# Power_supply.net
KiCad netlist of a schematic drawn in Altium Designer
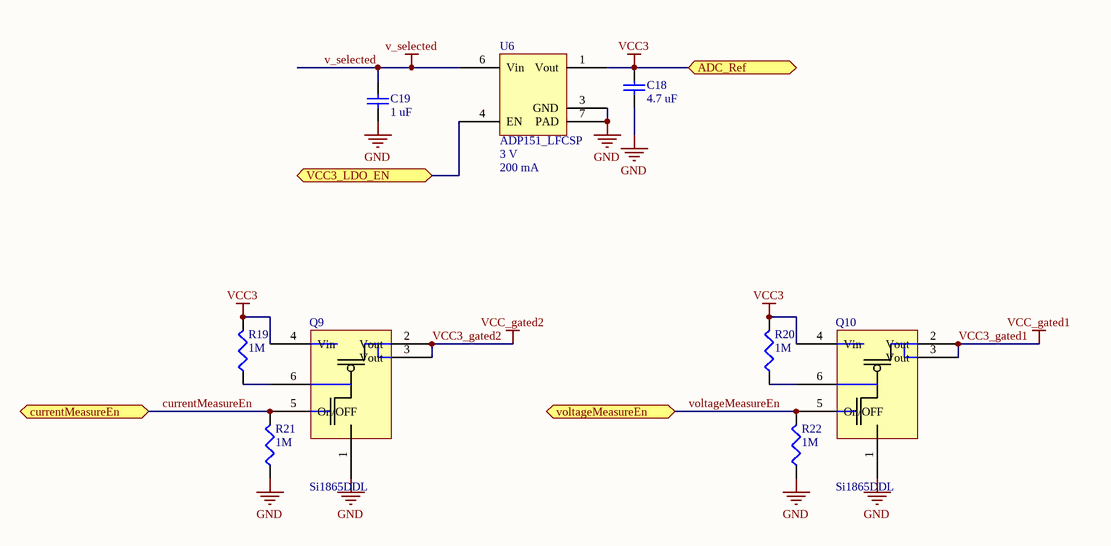
[diagram p0: Power_supply.SchDoc]

(export (version "E")
  (design (tool "Eeschema 10.0.6"))
  (components
    (comp (ref "C18")
      (value "4.7 uF")
      (footprint "0603")
      (description "Ceramic capacitor, 4.7u, 10V, 0603 package")
      (fields (field (name "TOLERANCE") "20%") (field (name "Comment") "Ceramic capacitor"))
      (libsource (lib "rlc") (part "C_4.7u_10V_0603_ceramic"))
    )
    (comp (ref "C19")
      (value "1 uF")
      (footprint "0402")
      (description "Ceramic capacitor, 1 uF, 16V, 0402 package")
      (fields (field (name "TOLERANCE") "10%") (field (name "Comment") "Ceramic capacitor"))
      (libsource (lib "rlc") (part "C_1u_16V_0402_ceramic"))
    )
    (comp (ref "Q9")
      (value "Si1865DDL")
      (footprint "SC70-6")
      (description "Load Switch with Level-Shift")
      (libsource (lib "power_switch") (part "Si1865DDL"))
    )
    (comp (ref "Q10")
      (value "Si1865DDL")
      (footprint "SC70-6")
      (description "Load Switch with Level-Shift")
      (libsource (lib "power_switch") (part "Si1865DDL"))
    )
    (comp (ref "R19")
      (value "1M")
      (footprint "0402")
      (description "Chip resistor, 1M, 0402 package")
      (fields (field (name "TOLERANCE") "1%") (field (name "POWER") "1/16 W"))
      (libsource (lib "rlc") (part "R_1M_0402"))
    )
    (comp (ref "R20")
      (value "1M")
      (footprint "0402")
      (description "Chip resistor, 1M, 0402 package")
      (fields (field (name "TOLERANCE") "1%") (field (name "POWER") "1/16 W"))
      (libsource (lib "rlc") (part "R_1M_0402"))
    )
    (comp (ref "R21")
      (value "1M")
      (footprint "0402")
      (description "Chip resistor, 1M, 0402 package")
      (fields (field (name "TOLERANCE") "1%") (field (name "POWER") "1/16 W"))
      (libsource (lib "rlc") (part "R_1M_0402"))
    )
    (comp (ref "R22")
      (value "1M")
      (footprint "0402")
      (description "Chip resistor, 1M, 0402 package")
      (fields (field (name "TOLERANCE") "1%") (field (name "POWER") "1/16 W"))
      (libsource (lib "rlc") (part "R_1M_0402"))
    )
    (comp (ref "U6")
      (value "ADP151_LFCSP")
      (footprint "CP-6-3")
      (description "Ultralow Noise, 200 mA,  CMOS Linear Regulator")
      (fields (field (name "VOLTAGE") "3 V") (field (name "CURRENT") "200 mA"))
      (libsource (lib "voltage_regulators") (part "ADP151_LFCSP"))
    )
  )
  (nets
    (net (code "1") (name "/VCC3_LDO_EN") (class "Default")
      (node (ref "U6") (pin "4") (pinfunction "EN_4") (pintype "passive"))
    )
    (net (code "2") (name "/currentMeasureEn") (class "Default")
      (node (ref "Q9") (pin "5") (pinfunction "On/OFF_5") (pintype "passive"))
      (node (ref "R21") (pin "1") (pintype "passive"))
    )
    (net (code "3") (name "/voltageMeasureEn") (class "Default")
      (node (ref "Q10") (pin "5") (pinfunction "On/OFF_5") (pintype "passive"))
      (node (ref "R22") (pin "1") (pintype "passive"))
    )
    (net (code "4") (name "GND") (class "Default")
      (node (ref "C18") (pin "2") (pintype "passive"))
      (node (ref "C19") (pin "2") (pintype "passive"))
      (node (ref "Q10") (pin "1") (pinfunction "S1_1") (pintype "passive"))
      (node (ref "Q9") (pin "1") (pinfunction "S1_1") (pintype "passive"))
      (node (ref "R21") (pin "2") (pintype "passive"))
      (node (ref "R22") (pin "2") (pintype "passive"))
      (node (ref "U6") (pin "3") (pinfunction "GND_3") (pintype "passive"))
      (node (ref "U6") (pin "7") (pinfunction "PAD_7") (pintype "passive"))
    )
    (net (code "5") (name "Net-(Q9-D1)") (class "Default")
      (node (ref "Q9") (pin "6") (pinfunction "D1_6") (pintype "passive"))
      (node (ref "R19") (pin "2") (pintype "passive"))
    )
    (net (code "6") (name "Net-(Q10-D1)") (class "Default")
      (node (ref "Q10") (pin "6") (pinfunction "D1_6") (pintype "passive"))
      (node (ref "R20") (pin "2") (pintype "passive"))
    )
    (net (code "7") (name "VCC3") (class "Default")
      (node (ref "C18") (pin "1") (pintype "passive"))
      (node (ref "Q10") (pin "4") (pinfunction "Vin_4") (pintype "passive"))
      (node (ref "Q9") (pin "4") (pinfunction "Vin_4") (pintype "passive"))
      (node (ref "R19") (pin "1") (pintype "passive"))
      (node (ref "R20") (pin "1") (pintype "passive"))
      (node (ref "U6") (pin "1") (pinfunction "Vout_1") (pintype "passive"))
    )
    (net (code "8") (name "VCC_gated1") (class "Default")
      (node (ref "Q10") (pin "2") (pinfunction "Vout_2") (pintype "passive"))
      (node (ref "Q10") (pin "3") (pinfunction "Vout_3") (pintype "passive"))
    )
    (net (code "9") (name "VCC_gated2") (class "Default")
      (node (ref "Q9") (pin "2") (pinfunction "Vout_2") (pintype "passive"))
      (node (ref "Q9") (pin "3") (pinfunction "Vout_3") (pintype "passive"))
    )
    (net (code "10") (name "v_selected") (class "Default")
      (node (ref "C19") (pin "1") (pintype "passive"))
      (node (ref "U6") (pin "6") (pinfunction "Vin_6") (pintype "passive"))
    )
  )
)
